# emu.net
KiCad netlist of a schematic drawn in Altium Designer
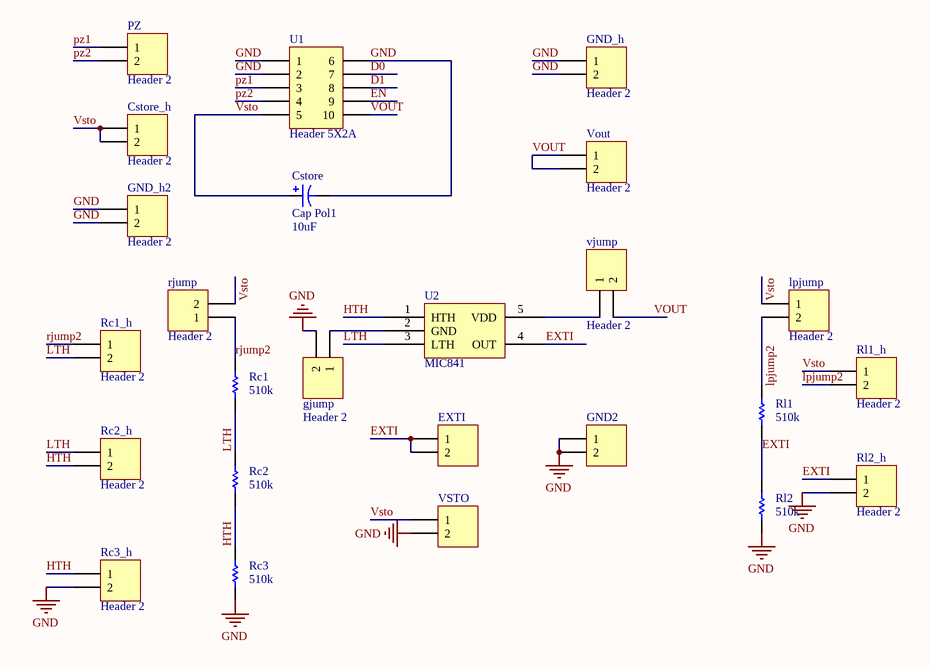
[diagram p0: emu.SchDoc]

(export (version "E")
  (design (tool "Eeschema 10.0.6"))
  (components
    (comp (ref "Cstore")
      (value "Cap Pol1")
      (footprint "ltc3588:直插电容")
      (description "Polarized Capacitor (Radial)")
      (fields (field (name "ALTIUM_VALUE") "10uF") (field (name "PUBLISHER") "Altium Limited"))
      (libsource (lib "Miscellaneous Devices") (part "Cap Pol1"))
    )
    (comp (ref "Cstore_h")
      (value "Header 2")
      (footprint "HDR1X2")
      (description "Header, 2-Pin")
      (fields (field (name "PUBLISHER") "Altium Limited"))
      (libsource (lib "") (part "Header 2_1"))
    )
    (comp (ref "EXTI")
      (value "Header 2")
      (footprint "HDR1X2")
      (description "Header, 2-Pin")
      (fields (field (name "PUBLISHER") "Altium Limited"))
      (libsource (lib "") (part "Header 2_1"))
    )
    (comp (ref "gjump")
      (value "Header 2")
      (footprint "HDR1X2")
      (description "Header, 2-Pin")
      (fields (field (name "PUBLISHER") "Altium Limited"))
      (libsource (lib "") (part "Header 2_2"))
    )
    (comp (ref "GND2")
      (value "Header 2")
      (footprint "HDR1X2")
      (description "Header, 2-Pin")
      (fields (field (name "PUBLISHER") "Altium Limited"))
      (libsource (lib "") (part "Header 2_1"))
    )
    (comp (ref "GND_h")
      (value "Header 2")
      (footprint "HDR1X2")
      (description "Header, 2-Pin")
      (fields (field (name "PUBLISHER") "Altium Limited"))
      (libsource (lib "") (part "Header 2_1"))
    )
    (comp (ref "GND_h2")
      (value "Header 2")
      (footprint "HDR1X2")
      (description "Header, 2-Pin")
      (fields (field (name "PUBLISHER") "Altium Limited"))
      (libsource (lib "") (part "Header 2_1"))
    )
    (comp (ref "lpjump")
      (value "Header 2")
      (footprint "HDR1X2")
      (description "Header, 2-Pin")
      (fields (field (name "PUBLISHER") "Altium Limited"))
      (libsource (lib "") (part "Header 2_1"))
    )
    (comp (ref "PZ")
      (value "Header 2")
      (footprint "HDR1X2")
      (description "Header, 2-Pin")
      (fields (field (name "PUBLISHER") "Altium Limited"))
      (libsource (lib "") (part "Header 2_1"))
    )
    (comp (ref "Rc1")
      (value "510k")
      (footprint "6-0805_N")
      (description "Resistor")
      (fields (field (name "Comment") "Res1") (field (name "PUBLISHER") "Altium Limited"))
      (libsource (lib "Miscellaneous Devices") (part "Res1"))
    )
    (comp (ref "Rc1_h")
      (value "Header 2")
      (footprint "HDR1X2")
      (description "Header, 2-Pin")
      (fields (field (name "PUBLISHER") "Altium Limited"))
      (libsource (lib "") (part "Header 2_1"))
    )
    (comp (ref "Rc2")
      (value "510k")
      (footprint "6-0805_N")
      (description "Resistor")
      (fields (field (name "Comment") "Res1") (field (name "PUBLISHER") "Altium Limited"))
      (libsource (lib "Miscellaneous Devices") (part "Res1"))
    )
    (comp (ref "Rc2_h")
      (value "Header 2")
      (footprint "HDR1X2")
      (description "Header, 2-Pin")
      (fields (field (name "PUBLISHER") "Altium Limited"))
      (libsource (lib "") (part "Header 2_1"))
    )
    (comp (ref "Rc3")
      (value "510k")
      (footprint "6-0805_N")
      (description "Resistor")
      (fields (field (name "Comment") "Res1") (field (name "PUBLISHER") "Altium Limited"))
      (libsource (lib "Miscellaneous Devices") (part "Res1"))
    )
    (comp (ref "Rc3_h")
      (value "Header 2")
      (footprint "HDR1X2")
      (description "Header, 2-Pin")
      (fields (field (name "PUBLISHER") "Altium Limited"))
      (libsource (lib "") (part "Header 2_1"))
    )
    (comp (ref "rjump")
      (value "Header 2")
      (footprint "HDR1X2")
      (description "Header, 2-Pin")
      (fields (field (name "PUBLISHER") "Altium Limited"))
      (libsource (lib "") (part "Header 2_3"))
    )
    (comp (ref "Rl1")
      (value "510k")
      (footprint "6-0805_N")
      (description "Resistor")
      (fields (field (name "Comment") "Res1") (field (name "PUBLISHER") "Altium Limited"))
      (libsource (lib "Miscellaneous Devices") (part "Res1"))
    )
    (comp (ref "Rl1_h")
      (value "Header 2")
      (footprint "HDR1X2")
      (description "Header, 2-Pin")
      (fields (field (name "PUBLISHER") "Altium Limited"))
      (libsource (lib "") (part "Header 2_1"))
    )
    (comp (ref "Rl2")
      (value "510k")
      (footprint "6-0805_N")
      (description "Resistor")
      (fields (field (name "Comment") "Res1") (field (name "PUBLISHER") "Altium Limited"))
      (libsource (lib "Miscellaneous Devices") (part "Res1"))
    )
    (comp (ref "Rl2_h")
      (value "Header 2")
      (footprint "HDR1X2")
      (description "Header, 2-Pin")
      (fields (field (name "PUBLISHER") "Altium Limited"))
      (libsource (lib "") (part "Header 2_1"))
    )
    (comp (ref "U1")
      (value "Header 5X2A")
      (footprint "ltc3588:ltc3588")
      (description "Header, 5-Pin, Dual row")
      (fields (field (name "PUBLISHER") "Altium Limited"))
      (libsource (lib "Miscellaneous Connectors") (part "Header 5X2A"))
    )
    (comp (ref "U2")
      (value "MIC841")
      (footprint "ltc3588:mic841")
      (libsource (lib "MIC841") (part "Component_1"))
    )
    (comp (ref "vjump")
      (value "Header 2")
      (footprint "HDR1X2")
      (description "Header, 2-Pin")
      (fields (field (name "PUBLISHER") "Altium Limited"))
      (libsource (lib "Miscellaneous Connectors") (part "Header 2"))
    )
    (comp (ref "Vout")
      (value "Header 2")
      (footprint "HDR1X2")
      (description "Header, 2-Pin")
      (fields (field (name "PUBLISHER") "Altium Limited"))
      (libsource (lib "") (part "Header 2_1"))
    )
    (comp (ref "VSTO")
      (value "Header 2")
      (footprint "HDR1X2")
      (description "Header, 2-Pin")
      (fields (field (name "PUBLISHER") "Altium Limited"))
      (libsource (lib "") (part "Header 2_1"))
    )
  )
  (nets
    (net (code "1") (name "/D0") (class "Default")
      (node (ref "U1") (pin "7") (pinfunction "7_7") (pintype "passive"))
    )
    (net (code "2") (name "/D1") (class "Default")
      (node (ref "U1") (pin "8") (pinfunction "8_8") (pintype "passive"))
    )
    (net (code "3") (name "/EN") (class "Default")
      (node (ref "U1") (pin "9") (pinfunction "9_9") (pintype "passive"))
    )
    (net (code "4") (name "/EXTI") (class "Default")
      (node (ref "EXTI") (pin "1") (pinfunction "1_1") (pintype "passive"))
      (node (ref "EXTI") (pin "2") (pinfunction "2_2") (pintype "passive"))
      (node (ref "Rl1") (pin "1") (pinfunction "1_1") (pintype "passive"))
      (node (ref "Rl2") (pin "2") (pinfunction "2_2") (pintype "passive"))
      (node (ref "Rl2_h") (pin "1") (pinfunction "1_1") (pintype "passive"))
      (node (ref "U2") (pin "4") (pinfunction "OUT_4") (pintype "passive"))
    )
    (net (code "5") (name "/HTH") (class "Default")
      (node (ref "Rc2") (pin "1") (pinfunction "1_1") (pintype "passive"))
      (node (ref "Rc2_h") (pin "2") (pinfunction "2_2") (pintype "passive"))
      (node (ref "Rc3") (pin "2") (pinfunction "2_2") (pintype "passive"))
      (node (ref "Rc3_h") (pin "1") (pinfunction "1_1") (pintype "passive"))
      (node (ref "U2") (pin "1") (pinfunction "HTH_1") (pintype "passive"))
    )
    (net (code "6") (name "/LTH") (class "Default")
      (node (ref "Rc1") (pin "1") (pinfunction "1_1") (pintype "passive"))
      (node (ref "Rc1_h") (pin "2") (pinfunction "2_2") (pintype "passive"))
      (node (ref "Rc2") (pin "2") (pinfunction "2_2") (pintype "passive"))
      (node (ref "Rc2_h") (pin "1") (pinfunction "1_1") (pintype "passive"))
      (node (ref "U2") (pin "3") (pinfunction "LTH_3") (pintype "passive"))
    )
    (net (code "7") (name "/VOUT") (class "Default")
      (node (ref "U1") (pin "10") (pinfunction "10_10") (pintype "passive"))
      (node (ref "Vout") (pin "1") (pinfunction "1_1") (pintype "passive"))
      (node (ref "Vout") (pin "2") (pinfunction "2_2") (pintype "passive"))
      (node (ref "vjump") (pin "2") (pinfunction "2_2") (pintype "passive"))
    )
    (net (code "8") (name "/Vsto") (class "Default")
      (node (ref "Cstore") (pin "1") (pinfunction "1_1") (pintype "passive"))
      (node (ref "Cstore_h") (pin "1") (pinfunction "1_1") (pintype "passive"))
      (node (ref "Cstore_h") (pin "2") (pinfunction "2_2") (pintype "passive"))
      (node (ref "Rl1_h") (pin "1") (pinfunction "1_1") (pintype "passive"))
      (node (ref "U1") (pin "5") (pinfunction "5_5") (pintype "passive"))
      (node (ref "VSTO") (pin "1") (pinfunction "1_1") (pintype "passive"))
      (node (ref "lpjump") (pin "1") (pinfunction "1_1") (pintype "passive"))
      (node (ref "rjump") (pin "2") (pinfunction "2_2") (pintype "passive"))
    )
    (net (code "9") (name "/lpjump2") (class "Default")
      (node (ref "Rl1") (pin "2") (pinfunction "2_2") (pintype "passive"))
      (node (ref "Rl1_h") (pin "2") (pinfunction "2_2") (pintype "passive"))
      (node (ref "lpjump") (pin "2") (pinfunction "2_2") (pintype "passive"))
    )
    (net (code "10") (name "/pz1") (class "Default")
      (node (ref "PZ") (pin "1") (pinfunction "1_1") (pintype "passive"))
      (node (ref "U1") (pin "3") (pinfunction "3_3") (pintype "passive"))
    )
    (net (code "11") (name "/pz2") (class "Default")
      (node (ref "PZ") (pin "2") (pinfunction "2_2") (pintype "passive"))
      (node (ref "U1") (pin "4") (pinfunction "4_4") (pintype "passive"))
    )
    (net (code "12") (name "/rjump2") (class "Default")
      (node (ref "Rc1") (pin "2") (pinfunction "2_2") (pintype "passive"))
      (node (ref "Rc1_h") (pin "1") (pinfunction "1_1") (pintype "passive"))
      (node (ref "rjump") (pin "1") (pinfunction "1_1") (pintype "passive"))
    )
    (net (code "13") (name "GND") (class "Default")
      (node (ref "Cstore") (pin "2") (pinfunction "2_2") (pintype "passive"))
      (node (ref "GND2") (pin "1") (pinfunction "1_1") (pintype "passive"))
      (node (ref "GND2") (pin "2") (pinfunction "2_2") (pintype "passive"))
      (node (ref "GND_h") (pin "1") (pinfunction "1_1") (pintype "passive"))
      (node (ref "GND_h") (pin "2") (pinfunction "2_2") (pintype "passive"))
      (node (ref "GND_h2") (pin "1") (pinfunction "1_1") (pintype "passive"))
      (node (ref "GND_h2") (pin "2") (pinfunction "2_2") (pintype "passive"))
      (node (ref "Rc3") (pin "1") (pinfunction "1_1") (pintype "passive"))
      (node (ref "Rc3_h") (pin "2") (pinfunction "2_2") (pintype "passive"))
      (node (ref "Rl2") (pin "1") (pinfunction "1_1") (pintype "passive"))
      (node (ref "Rl2_h") (pin "2") (pinfunction "2_2") (pintype "passive"))
      (node (ref "U1") (pin "1") (pinfunction "1_1") (pintype "passive"))
      (node (ref "U1") (pin "2") (pinfunction "2_2") (pintype "passive"))
      (node (ref "U1") (pin "6") (pinfunction "6_6") (pintype "passive"))
      (node (ref "VSTO") (pin "2") (pinfunction "2_2") (pintype "passive"))
      (node (ref "gjump") (pin "2") (pinfunction "2_2") (pintype "passive"))
    )
    (net (code "14") (name "Net-(U2-GND)") (class "Default")
      (node (ref "U2") (pin "2") (pinfunction "GND_2") (pintype "passive"))
      (node (ref "gjump") (pin "1") (pinfunction "1_1") (pintype "passive"))
    )
    (net (code "15") (name "Net-(U2-VDD)") (class "Default")
      (node (ref "U2") (pin "5") (pinfunction "VDD_5") (pintype "passive"))
      (node (ref "vjump") (pin "1") (pinfunction "1_1") (pintype "passive"))
    )
  )
)
